# Sheet1.net
KiCad netlist of a schematic drawn in Altium Designer
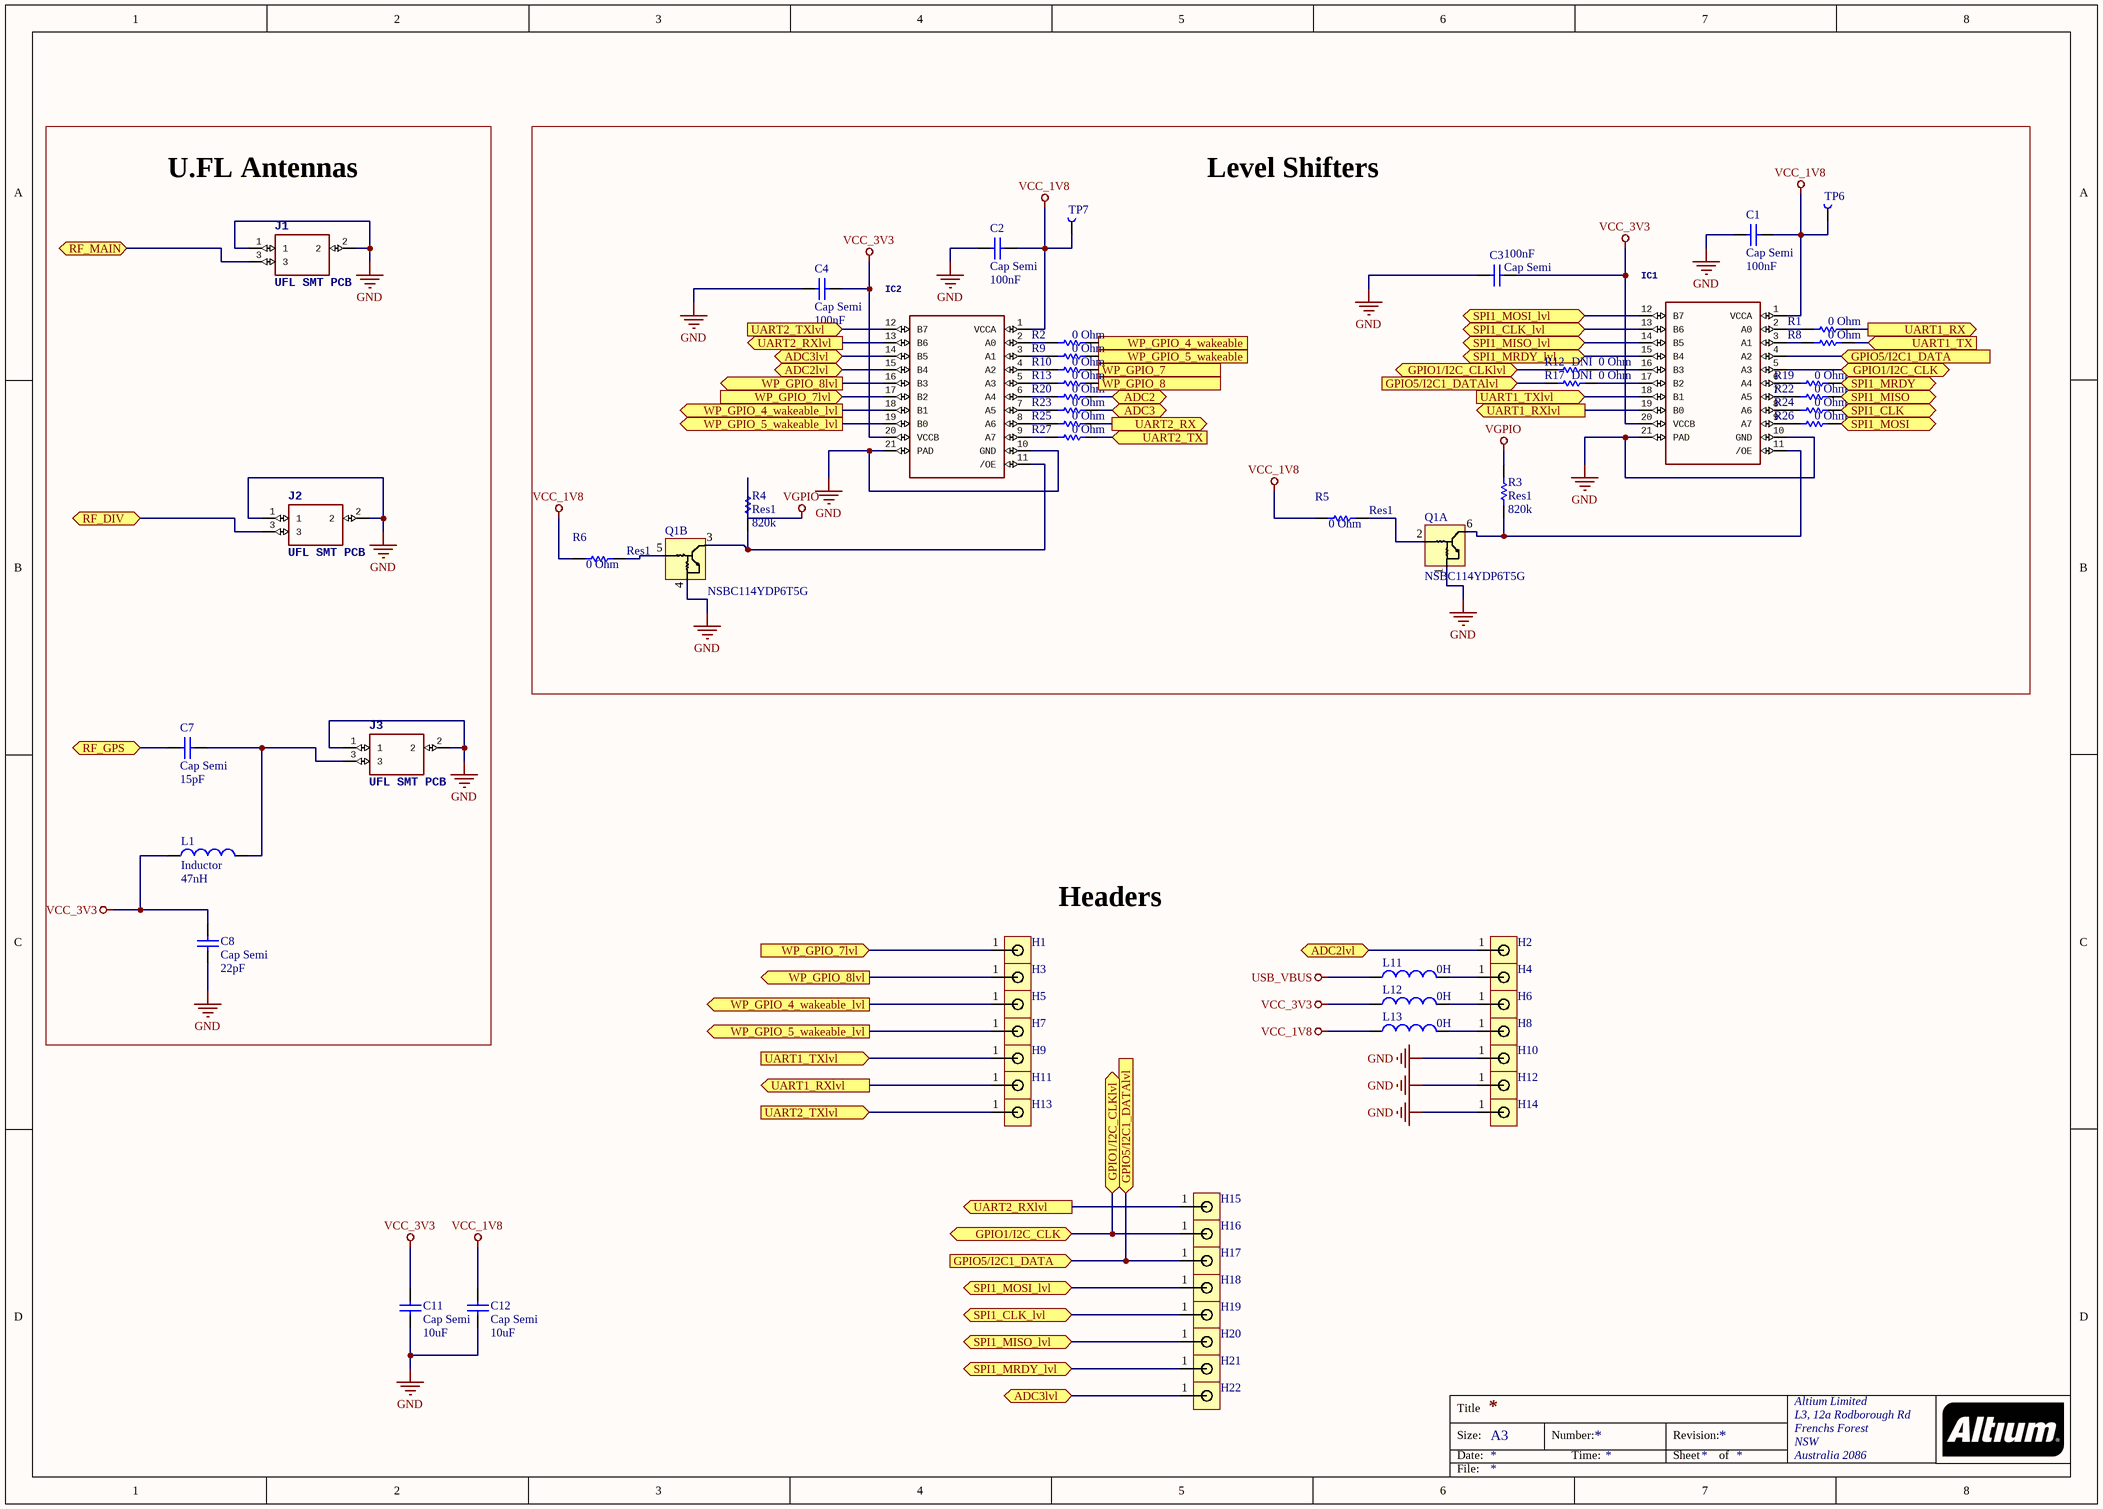
[diagram p0: Sheet1.SchDoc]

(export (version "E")
  (design (tool "Eeschema 10.0.6"))
  (components
    (comp (ref "C1")
      (value "Cap Semi")
      (footprint "CAP 0402/1005")
      (description "0.1µF -20%, +80% 16V Ceramic Capacitor Y5V (F) 0402 (1005 Metric)")
      (fields (field (name "PART NUMBER") "VJ0402V104ZXJCW1BC") (field (name "ALTIUM_VALUE") "100nF"))
      (libsource (lib "Miscellaneous Devices") (part "Cap Semi"))
    )
    (comp (ref "C2")
      (value "Cap Semi")
      (footprint "CAP 0402/1005")
      (description "0.1µF -20%, +80% 16V Ceramic Capacitor Y5V (F) 0402 (1005 Metric)")
      (fields (field (name "PART NUMBER") "VJ0402V104ZXJCW1BC") (field (name "ALTIUM_VALUE") "100nF"))
      (libsource (lib "Miscellaneous Devices") (part "Cap Semi"))
    )
    (comp (ref "C3")
      (value "Cap Semi")
      (footprint "CAP 0402/1005")
      (description "0.1µF -20%, +80% 16V Ceramic Capacitor Y5V (F) 0402 (1005 Metric)")
      (fields (field (name "PART NUMBER") "VJ0402V104ZXJCW1BC") (field (name "ALTIUM_VALUE") "100nF"))
      (libsource (lib "Miscellaneous Devices") (part "Cap Semi"))
    )
    (comp (ref "C4")
      (value "Cap Semi")
      (footprint "CAP 0402/1005")
      (description "0.1µF -20%, +80% 16V Ceramic Capacitor Y5V (F) 0402 (1005 Metric)")
      (fields (field (name "PART NUMBER") "VJ0402V104ZXJCW1BC") (field (name "ALTIUM_VALUE") "100nF"))
      (libsource (lib "Miscellaneous Devices") (part "Cap Semi"))
    )
    (comp (ref "C7")
      (value "Cap Semi")
      (footprint "CAP 0402/1005")
      (description "15pF ±5% 50V Ceramic Capacitor C0G, NP0 0402 (1005 Metric)")
      (fields (field (name "PART NUMBER") "UMK105CG150JV-F") (field (name "ALTIUM_VALUE") "15pF"))
      (libsource (lib "Miscellaneous Devices") (part "Cap Semi"))
    )
    (comp (ref "C8")
      (value "Cap Semi")
      (footprint "CAP 0402/1005")
      (description "CAP CER 22PF 50V NP0 0402")
      (fields (field (name "PART NUMBER") "UMK105CG220JV-F") (field (name "ALTIUM_VALUE") "22pF"))
      (libsource (lib "Miscellaneous Devices") (part "Cap Semi"))
    )
    (comp (ref "C11")
      (value "Cap Semi")
      (footprint "CAP 0603/1608")
      (description "10µF ±20% 6.3V Ceramic Capacitor X5R 0603 (1608 Metric)")
      (fields
        (field (name "PART NUMBER") "JMK107BJ106MA-T")
        (field (name "ALTIUM_VALUE") "10uF")
        (field (name "PUBLISHER") "Altium Limited")
      )
      (libsource (lib "Miscellaneous Devices") (part "Cap Semi"))
    )
    (comp (ref "C12")
      (value "Cap Semi")
      (footprint "CAP 0603/1608")
      (description "10µF ±20% 6.3V Ceramic Capacitor X5R 0603 (1608 Metric)")
      (fields
        (field (name "PART NUMBER") "JMK107BJ106MA-T")
        (field (name "ALTIUM_VALUE") "10uF")
        (field (name "PUBLISHER") "Altium Limited")
      )
      (libsource (lib "Miscellaneous Devices") (part "Cap Semi"))
    )
    (comp (ref "H1") (value "Header 1") (footprint "PIN1-3D") (libsource (lib "Header 1") (part "Header 1")))
    (comp (ref "H2") (value "Header 1") (footprint "PIN1-3D") (libsource (lib "Header 1") (part "Header 1")))
    (comp (ref "H3") (value "Header 1") (footprint "PIN1-3D") (libsource (lib "Header 1") (part "Header 1")))
    (comp (ref "H4") (value "Header 1") (footprint "PIN1-3D") (libsource (lib "Header 1") (part "Header 1")))
    (comp (ref "H5") (value "Header 1") (footprint "PIN1-3D") (libsource (lib "Header 1") (part "Header 1")))
    (comp (ref "H6") (value "Header 1") (footprint "PIN1-3D") (libsource (lib "Header 1") (part "Header 1")))
    (comp (ref "H7") (value "Header 1") (footprint "PIN1-3D") (libsource (lib "Header 1") (part "Header 1")))
    (comp (ref "H8") (value "Header 1") (footprint "PIN1-3D") (libsource (lib "Header 1") (part "Header 1")))
    (comp (ref "H9") (value "Header 1") (footprint "PIN1-3D") (libsource (lib "Header 1") (part "Header 1")))
    (comp (ref "H10") (value "Header 1") (footprint "PIN1-3D") (libsource (lib "Header 1") (part "Header 1")))
    (comp (ref "H11") (value "Header 1") (footprint "PIN1-3D") (libsource (lib "Header 1") (part "Header 1")))
    (comp (ref "H12") (value "Header 1") (footprint "PIN1-3D") (libsource (lib "Header 1") (part "Header 1")))
    (comp (ref "H13") (value "Header 1") (footprint "PIN1-3D") (libsource (lib "Header 1") (part "Header 1")))
    (comp (ref "H14") (value "Header 1") (footprint "PIN1-3D") (libsource (lib "Header 1") (part "Header 1")))
    (comp (ref "H15") (value "Header 1") (footprint "PIN1-3D") (libsource (lib "Header 1") (part "Header 1")))
    (comp (ref "H16") (value "Header 1") (footprint "PIN1-3D") (libsource (lib "Header 1") (part "Header 1")))
    (comp (ref "H17") (value "Header 1") (footprint "PIN1-3D") (libsource (lib "Header 1") (part "Header 1")))
    (comp (ref "H18") (value "Header 1") (footprint "PIN1-3D") (libsource (lib "Header 1") (part "Header 1")))
    (comp (ref "H19") (value "Header 1") (footprint "PIN1-3D") (libsource (lib "Header 1") (part "Header 1")))
    (comp (ref "H20") (value "Header 1") (footprint "PIN1-3D") (libsource (lib "Header 1") (part "Header 1")))
    (comp (ref "H21") (value "Header 1") (footprint "PIN1-3D") (libsource (lib "Header 1") (part "Header 1")))
    (comp (ref "H22") (value "Header 1") (footprint "PIN1-3D") (libsource (lib "Header 1") (part "Header 1")))
    (comp (ref "IC1")
      (value "~")
      (footprint "DQFN-20")
      (description "Voltage Level Translator Bidirectional 1 Circuit 8 Channel 100Mbps 20-DQFN (2.5x4.5)")
      (fields (field (name "PART NUMBER") "FXMA108BQX") (field (name "MOUSER_PART_NUMBER") "512-FXMA108BQX"))
      (libsource (lib "FXMA108BQX") (part "FXMA108BQX"))
    )
    (comp (ref "IC2")
      (value "~")
      (footprint "DQFN-20")
      (description "Voltage Level Translator Bidirectional 1 Circuit 8 Channel 100Mbps 20-DQFN (2.5x4.5)")
      (fields (field (name "PART NUMBER") "FXMA108BQX") (field (name "MOUSER_PART_NUMBER") "512-FXMA108BQX"))
      (libsource (lib "FXMA108BQX") (part "FXMA108BQX"))
    )
    (comp (ref "J1")
      (value "UFL SMT PCB")
      (footprint "U.FL-R-SMT-1(10)")
      (description "U.FL (UMCC), IPEX MHF1 Connector Receptacle, Male Pin 50 Ohm Surface Mount Solder")
      (fields
        (field (name "PART NUMBER") "20279-001E-01")
        (field (name "MANUFACTURER_PART_NUMBER") "U.FL-R-SMT-1(10)")
      )
      (libsource (lib "U.FL-R-SMT-1(10)") (part "U.FL-R-SMT-1(10)"))
    )
    (comp (ref "J2")
      (value "UFL SMT PCB")
      (footprint "U.FL-R-SMT-1(10)")
      (description "U.FL (UMCC), IPEX MHF1 Connector Receptacle, Male Pin 50 Ohm Surface Mount Solder")
      (fields
        (field (name "PART NUMBER") "20279-001E-01")
        (field (name "MANUFACTURER_PART_NUMBER") "U.FL-R-SMT-1(10)")
      )
      (libsource (lib "U.FL-R-SMT-1(10)") (part "U.FL-R-SMT-1(10)"))
    )
    (comp (ref "J3")
      (value "UFL SMT PCB")
      (footprint "U.FL-R-SMT-1(10)")
      (description "U.FL (UMCC), IPEX MHF1 Connector Receptacle, Male Pin 50 Ohm Surface Mount Solder")
      (fields
        (field (name "PART NUMBER") "20279-001E-01")
        (field (name "MANUFACTURER_PART_NUMBER") "U.FL-R-SMT-1(10)")
      )
      (libsource (lib "U.FL-R-SMT-1(10)") (part "U.FL-R-SMT-1(10)"))
    )
    (comp (ref "L1")
      (value "Inductor")
      (footprint "IND 0402/1005 RF WW")
      (description "47nH Unshielded Multilayer Inductor 250mA 1.15 Ohm Max 0402 (1005 Metric)")
      (fields (field (name "PART NUMBER") "LQG15HN47NJ02D") (field (name "ALTIUM_VALUE") "47nH"))
      (libsource (lib "Miscellaneous Devices") (part "Inductor"))
    )
    (comp (ref "L11")
      (value "0H")
      (footprint "INDC1608L")
      (description "220 Ohms @ 100MHz 1 Power Line Ferrite Bead 0603 (1608 Metric) 2.2A 50 mOhm")
      (fields
        (field (name "PART NUMBER") "MPZ1608S221ATA00")
        (field (name "Comment") "Inductor")
        (field (name "PUBLISHER") "Altium Limited")
      )
      (libsource (lib "Miscellaneous Devices") (part "Inductor"))
    )
    (comp (ref "L12")
      (value "0H")
      (footprint "INDC1608L")
      (description "220 Ohms @ 100MHz 1 Power Line Ferrite Bead 0603 (1608 Metric) 2.2A 50 mOhm")
      (fields
        (field (name "PART NUMBER") "MPZ1608S221ATA00")
        (field (name "Comment") "Inductor")
        (field (name "PUBLISHER") "Altium Limited")
      )
      (libsource (lib "Miscellaneous Devices") (part "Inductor"))
    )
    (comp (ref "L13")
      (value "0H")
      (footprint "INDC1608L")
      (description "220 Ohms @ 100MHz 1 Power Line Ferrite Bead 0603 (1608 Metric) 2.2A 50 mOhm")
      (fields
        (field (name "PART NUMBER") "MPZ1608S221ATA00")
        (field (name "Comment") "Inductor")
        (field (name "PUBLISHER") "Altium Limited")
      )
      (libsource (lib "Miscellaneous Devices") (part "Inductor"))
    )
    (comp (ref "Q1")
      (value "NSBC114YDP6T5G")
      (footprint "NSBC114YDP6T5G")
      (libsource (lib "") (part "NSBC114YDP6T5G_1"))
    )
    (comp (ref "R1")
      (value "0 Ohm")
      (footprint "RES 0402/1005")
      (description "0 Ohms Jumper  Chip Resistor 0402 (1005 Metric) Automotive AEC-Q200 Metal Element")
      (fields (field (name "PART NUMBER") "RK73Z1ETTP") (field (name "Comment") "Res1"))
      (libsource (lib "Miscellaneous Devices") (part "Res1"))
    )
    (comp (ref "R2")
      (value "0 Ohm")
      (footprint "RES 0402/1005")
      (description "0 Ohms Jumper  Chip Resistor 0402 (1005 Metric) Automotive AEC-Q200 Metal Element")
      (fields (field (name "PART NUMBER") "RK73Z1ETTP") (field (name "Comment") "Res1"))
      (libsource (lib "Miscellaneous Devices") (part "Res1"))
    )
    (comp (ref "R3")
      (value "Res1")
      (footprint "RES 0402/1005")
      (description "820 kOhms ±1% 0.063W, 1/16W Chip Resistor 0402 (1005 Metric) Moisture Resistant Thick Film")
      (fields (field (name "PART NUMBER") "RC0402FR-07820KL") (field (name "ALTIUM_VALUE") "820k"))
      (libsource (lib "Miscellaneous Devices") (part "Res1"))
    )
    (comp (ref "R4")
      (value "Res1")
      (footprint "RES 0402/1005")
      (description "820 kOhms ±1% 0.063W, 1/16W Chip Resistor 0402 (1005 Metric) Moisture Resistant Thick Film")
      (fields (field (name "PART NUMBER") "RC0402FR-07820KL") (field (name "ALTIUM_VALUE") "820k"))
      (libsource (lib "Miscellaneous Devices") (part "Res1"))
    )
    (comp (ref "R5")
      (value "Res1")
      (footprint "RES 0402/1005")
      (description "0 Ohms Jumper  Chip Resistor 0402 (1005 Metric) Automotive AEC-Q200 Metal Element")
      (fields (field (name "PART NUMBER") "RK73Z1ETTP") (field (name "ALTIUM_VALUE") "0 Ohm"))
      (libsource (lib "Miscellaneous Devices") (part "Res1"))
    )
    (comp (ref "R6")
      (value "Res1")
      (footprint "RES 0402/1005")
      (description "0 Ohms Jumper  Chip Resistor 0402 (1005 Metric) Automotive AEC-Q200 Metal Element")
      (fields (field (name "PART NUMBER") "RK73Z1ETTP") (field (name "ALTIUM_VALUE") "0 Ohm"))
      (libsource (lib "Miscellaneous Devices") (part "Res1"))
    )
    (comp (ref "R8")
      (value "0 Ohm")
      (footprint "RES 0402/1005")
      (description "0 Ohms Jumper  Chip Resistor 0402 (1005 Metric) Automotive AEC-Q200 Metal Element")
      (fields (field (name "PART NUMBER") "RK73Z1ETTP") (field (name "Comment") "Res1"))
      (libsource (lib "Miscellaneous Devices") (part "Res1"))
    )
    (comp (ref "R9")
      (value "0 Ohm")
      (footprint "RES 0402/1005")
      (description "0 Ohms Jumper  Chip Resistor 0402 (1005 Metric) Automotive AEC-Q200 Metal Element")
      (fields (field (name "PART NUMBER") "RK73Z1ETTP") (field (name "Comment") "Res1"))
      (libsource (lib "Miscellaneous Devices") (part "Res1"))
    )
    (comp (ref "R10")
      (value "0 Ohm")
      (footprint "RES 0402/1005")
      (description "0 Ohms Jumper  Chip Resistor 0402 (1005 Metric) Automotive AEC-Q200 Metal Element")
      (fields (field (name "PART NUMBER") "RK73Z1ETTP") (field (name "Comment") "Res1"))
      (libsource (lib "Miscellaneous Devices") (part "Res1"))
    )
    (comp (ref "R12")
      (value "DNI")
      (footprint "RES 0402/1005")
      (description "0 Ohms Jumper  Chip Resistor 0402 (1005 Metric) Automotive AEC-Q200 Metal Element")
      (fields (field (name "PART NUMBER") "RK73Z1ETTP") (field (name "ALTIUM_VALUE") "0 Ohm"))
      (libsource (lib "Miscellaneous Devices") (part "Res1"))
    )
    (comp (ref "R13")
      (value "0 Ohm")
      (footprint "RES 0402/1005")
      (description "0 Ohms Jumper  Chip Resistor 0402 (1005 Metric) Automotive AEC-Q200 Metal Element")
      (fields (field (name "PART NUMBER") "RK73Z1ETTP") (field (name "Comment") "Res1"))
      (libsource (lib "Miscellaneous Devices") (part "Res1"))
    )
    (comp (ref "R17")
      (value "DNI")
      (footprint "RES 0402/1005")
      (description "0 Ohms Jumper  Chip Resistor 0402 (1005 Metric) Automotive AEC-Q200 Metal Element")
      (fields (field (name "PART NUMBER") "RK73Z1ETTP") (field (name "ALTIUM_VALUE") "0 Ohm"))
      (libsource (lib "Miscellaneous Devices") (part "Res1"))
    )
    (comp (ref "R19")
      (value "0 Ohm")
      (footprint "RES 0402/1005")
      (description "0 Ohms Jumper  Chip Resistor 0402 (1005 Metric) Automotive AEC-Q200 Metal Element")
      (fields (field (name "PART NUMBER") "RK73Z1ETTP") (field (name "Comment") "Res1"))
      (libsource (lib "Miscellaneous Devices") (part "Res1"))
    )
    (comp (ref "R20")
      (value "0 Ohm")
      (footprint "RES 0402/1005")
      (description "0 Ohms Jumper  Chip Resistor 0402 (1005 Metric) Automotive AEC-Q200 Metal Element")
      (fields (field (name "PART NUMBER") "RK73Z1ETTP") (field (name "Comment") "Res1"))
      (libsource (lib "Miscellaneous Devices") (part "Res1"))
    )
    (comp (ref "R22")
      (value "0 Ohm")
      (footprint "RES 0402/1005")
      (description "0 Ohms Jumper  Chip Resistor 0402 (1005 Metric) Automotive AEC-Q200 Metal Element")
      (fields (field (name "PART NUMBER") "RK73Z1ETTP") (field (name "Comment") "Res1"))
      (libsource (lib "Miscellaneous Devices") (part "Res1"))
    )
    (comp (ref "R23")
      (value "0 Ohm")
      (footprint "RES 0402/1005")
      (description "0 Ohms Jumper  Chip Resistor 0402 (1005 Metric) Automotive AEC-Q200 Metal Element")
      (fields (field (name "PART NUMBER") "RK73Z1ETTP") (field (name "Comment") "Res1"))
      (libsource (lib "Miscellaneous Devices") (part "Res1"))
    )
    (comp (ref "R24")
      (value "0 Ohm")
      (footprint "RES 0402/1005")
      (description "0 Ohms Jumper  Chip Resistor 0402 (1005 Metric) Automotive AEC-Q200 Metal Element")
      (fields (field (name "PART NUMBER") "RK73Z1ETTP") (field (name "Comment") "Res1"))
      (libsource (lib "Miscellaneous Devices") (part "Res1"))
    )
    (comp (ref "R25")
      (value "0 Ohm")
      (footprint "RES 0402/1005")
      (description "0 Ohms Jumper  Chip Resistor 0402 (1005 Metric) Automotive AEC-Q200 Metal Element")
      (fields (field (name "PART NUMBER") "RK73Z1ETTP") (field (name "Comment") "Res1"))
      (libsource (lib "Miscellaneous Devices") (part "Res1"))
    )
    (comp (ref "R26")
      (value "0 Ohm")
      (footprint "RES 0402/1005")
      (description "0 Ohms Jumper  Chip Resistor 0402 (1005 Metric) Automotive AEC-Q200 Metal Element")
      (fields (field (name "PART NUMBER") "RK73Z1ETTP") (field (name "Comment") "Res1"))
      (libsource (lib "Miscellaneous Devices") (part "Res1"))
    )
    (comp (ref "R27")
      (value "0 Ohm")
      (footprint "RES 0402/1005")
      (description "0 Ohms Jumper  Chip Resistor 0402 (1005 Metric) Automotive AEC-Q200 Metal Element")
      (fields (field (name "PART NUMBER") "RK73Z1ETTP") (field (name "Comment") "Res1"))
      (libsource (lib "Miscellaneous Devices") (part "Res1"))
    )
    (comp (ref "TP6")
      (value "TestPoint")
      (footprint "TestPoint")
      (libsource (lib "TestPoint") (part "TestPoint"))
    )
    (comp (ref "TP7")
      (value "TestPoint")
      (footprint "TestPoint")
      (libsource (lib "TestPoint") (part "TestPoint"))
    )
  )
  (nets
    (net (code "1") (name "/ADC2") (class "Default")
      (node (ref "R20") (pin "2") (pinfunction "2_2") (pintype "passive"))
    )
    (net (code "2") (name "/ADC2lvl") (class "Default")
      (node (ref "H2") (pin "1") (pinfunction "1_1") (pintype "passive"))
      (node (ref "IC2") (pin "15") (pinfunction "B4_15") (pintype "bidirectional"))
    )
    (net (code "3") (name "/ADC3") (class "Default")
      (node (ref "R23") (pin "2") (pinfunction "2_2") (pintype "passive"))
    )
    (net (code "4") (name "/ADC3lvl") (class "Default")
      (node (ref "H22") (pin "1") (pinfunction "1_1") (pintype "passive"))
      (node (ref "IC2") (pin "14") (pinfunction "B5_14") (pintype "bidirectional"))
    )
    (net (code "5") (name "/GPIO1{slash}I2C_CLK") (class "Default")
      (node (ref "H16") (pin "1") (pinfunction "1_1") (pintype "passive"))
      (node (ref "IC1") (pin "5") (pinfunction "A3_5") (pintype "bidirectional"))
      (node (ref "R12") (pin "1") (pinfunction "1_1") (pintype "passive"))
    )
    (net (code "6") (name "/GPIO5{slash}I2C1_DATA") (class "Default")
      (node (ref "H17") (pin "1") (pinfunction "1_1") (pintype "passive"))
      (node (ref "IC1") (pin "4") (pinfunction "A2_4") (pintype "bidirectional"))
      (node (ref "R17") (pin "1") (pinfunction "1_1") (pintype "passive"))
    )
    (net (code "7") (name "/RF_DIV") (class "Default")
      (node (ref "J2") (pin "3") (pinfunction "3_3") (pintype "bidirectional"))
    )
    (net (code "8") (name "/RF_GPS") (class "Default")
      (node (ref "C7") (pin "2") (pinfunction "2_2") (pintype "passive"))
    )
    (net (code "9") (name "/RF_MAIN") (class "Default")
      (node (ref "J1") (pin "3") (pinfunction "3_3") (pintype "bidirectional"))
    )
    (net (code "10") (name "/SPI1_CLK") (class "Default")
      (node (ref "R24") (pin "2") (pinfunction "2_2") (pintype "passive"))
    )
    (net (code "11") (name "/SPI1_CLK_lvl") (class "Default")
      (node (ref "H19") (pin "1") (pinfunction "1_1") (pintype "passive"))
      (node (ref "IC1") (pin "13") (pinfunction "B6_13") (pintype "bidirectional"))
    )
    (net (code "12") (name "/SPI1_MISO") (class "Default")
      (node (ref "R22") (pin "2") (pinfunction "2_2") (pintype "passive"))
    )
    (net (code "13") (name "/SPI1_MISO_lvl") (class "Default")
      (node (ref "H20") (pin "1") (pinfunction "1_1") (pintype "passive"))
      (node (ref "IC1") (pin "14") (pinfunction "B5_14") (pintype "bidirectional"))
    )
    (net (code "14") (name "/SPI1_MOSI") (class "Default")
      (node (ref "R26") (pin "2") (pinfunction "2_2") (pintype "passive"))
    )
    (net (code "15") (name "/SPI1_MOSI_lvl") (class "Default")
      (node (ref "H18") (pin "1") (pinfunction "1_1") (pintype "passive"))
      (node (ref "IC1") (pin "12") (pinfunction "B7_12") (pintype "bidirectional"))
    )
    (net (code "16") (name "/SPI1_MRDY") (class "Default")
      (node (ref "R19") (pin "2") (pinfunction "2_2") (pintype "passive"))
    )
    (net (code "17") (name "/SPI1_MRDY_lvl") (class "Default")
      (node (ref "H21") (pin "1") (pinfunction "1_1") (pintype "passive"))
      (node (ref "IC1") (pin "15") (pinfunction "B4_15") (pintype "bidirectional"))
    )
    (net (code "18") (name "/UART1_RX") (class "Default")
      (node (ref "R1") (pin "2") (pinfunction "2_2") (pintype "passive"))
    )
    (net (code "19") (name "/UART1_RXlvl") (class "Default")
      (node (ref "H11") (pin "1") (pinfunction "1_1") (pintype "passive"))
      (node (ref "IC1") (pin "19") (pinfunction "B0_19") (pintype "bidirectional"))
    )
    (net (code "20") (name "/UART1_TX") (class "Default")
      (node (ref "R8") (pin "2") (pinfunction "2_2") (pintype "passive"))
    )
    (net (code "21") (name "/UART1_TXlvl") (class "Default")
      (node (ref "H9") (pin "1") (pinfunction "1_1") (pintype "passive"))
      (node (ref "IC1") (pin "18") (pinfunction "B1_18") (pintype "bidirectional"))
    )
    (net (code "22") (name "/UART2_RX") (class "Default")
      (node (ref "R25") (pin "2") (pinfunction "2_2") (pintype "passive"))
    )
    (net (code "23") (name "/UART2_RXlvl") (class "Default")
      (node (ref "H15") (pin "1") (pinfunction "1_1") (pintype "passive"))
      (node (ref "IC2") (pin "13") (pinfunction "B6_13") (pintype "bidirectional"))
    )
    (net (code "24") (name "/UART2_TX") (class "Default")
      (node (ref "R27") (pin "2") (pinfunction "2_2") (pintype "passive"))
    )
    (net (code "25") (name "/UART2_TXlvl") (class "Default")
      (node (ref "H13") (pin "1") (pinfunction "1_1") (pintype "passive"))
      (node (ref "IC2") (pin "12") (pinfunction "B7_12") (pintype "bidirectional"))
    )
    (net (code "26") (name "/WP_GPIO_4_wakeable") (class "Default")
      (node (ref "R2") (pin "2") (pinfunction "2_2") (pintype "passive"))
    )
    (net (code "27") (name "/WP_GPIO_4_wakeable_lvl") (class "Default")
      (node (ref "H5") (pin "1") (pinfunction "1_1") (pintype "passive"))
      (node (ref "IC2") (pin "18") (pinfunction "B1_18") (pintype "bidirectional"))
    )
    (net (code "28") (name "/WP_GPIO_5_wakeable") (class "Default")
      (node (ref "R9") (pin "2") (pinfunction "2_2") (pintype "passive"))
    )
    (net (code "29") (name "/WP_GPIO_5_wakeable_lvl") (class "Default")
      (node (ref "H7") (pin "1") (pinfunction "1_1") (pintype "passive"))
      (node (ref "IC2") (pin "19") (pinfunction "B0_19") (pintype "bidirectional"))
    )
    (net (code "30") (name "/WP_GPIO_7") (class "Default")
      (node (ref "R10") (pin "2") (pinfunction "2_2") (pintype "passive"))
    )
    (net (code "31") (name "/WP_GPIO_7lvl") (class "Default")
      (node (ref "H1") (pin "1") (pinfunction "1_1") (pintype "passive"))
      (node (ref "IC2") (pin "17") (pinfunction "B2_17") (pintype "bidirectional"))
    )
    (net (code "32") (name "/WP_GPIO_8") (class "Default")
      (node (ref "R13") (pin "2") (pinfunction "2_2") (pintype "passive"))
    )
    (net (code "33") (name "/WP_GPIO_8lvl") (class "Default")
      (node (ref "H3") (pin "1") (pinfunction "1_1") (pintype "passive"))
      (node (ref "IC2") (pin "16") (pinfunction "B3_16") (pintype "bidirectional"))
    )
    (net (code "34") (name "GND") (class "Default")
      (node (ref "C1") (pin "2") (pinfunction "2_2") (pintype "passive"))
      (node (ref "C11") (pin "1") (pinfunction "1_1") (pintype "passive"))
      (node (ref "C12") (pin "1") (pinfunction "1_1") (pintype "passive"))
      (node (ref "C2") (pin "2") (pinfunction "2_2") (pintype "passive"))
      (node (ref "C3") (pin "2") (pinfunction "2_2") (pintype "passive"))
      (node (ref "C4") (pin "2") (pinfunction "2_2") (pintype "passive"))
      (node (ref "C8") (pin "2") (pinfunction "2_2") (pintype "passive"))
      (node (ref "H10") (pin "1") (pinfunction "1_1") (pintype "passive"))
      (node (ref "H12") (pin "1") (pinfunction "1_1") (pintype "passive"))
      (node (ref "H14") (pin "1") (pinfunction "1_1") (pintype "passive"))
      (node (ref "IC1") (pin "10") (pinfunction "GND_10") (pintype "bidirectional"))
      (node (ref "IC1") (pin "21") (pinfunction "PAD_21") (pintype "bidirectional"))
      (node (ref "IC2") (pin "10") (pinfunction "GND_10") (pintype "bidirectional"))
      (node (ref "IC2") (pin "21") (pinfunction "PAD_21") (pintype "bidirectional"))
      (node (ref "J1") (pin "1") (pinfunction "1_1") (pintype "bidirectional"))
      (node (ref "J1") (pin "2") (pinfunction "2_2") (pintype "bidirectional"))
      (node (ref "J2") (pin "1") (pinfunction "1_1") (pintype "bidirectional"))
      (node (ref "J2") (pin "2") (pinfunction "2_2") (pintype "bidirectional"))
      (node (ref "J3") (pin "1") (pinfunction "1_1") (pintype "bidirectional"))
      (node (ref "J3") (pin "2") (pinfunction "2_2") (pintype "bidirectional"))
      (node (ref "Q1") (pin "1") (pintype "passive"))
      (node (ref "Q1") (pin "4") (pintype "passive"))
    )
    (net (code "35") (name "Net-(C7-Pad1)") (class "Default")
      (node (ref "C7") (pin "1") (pinfunction "1_1") (pintype "passive"))
      (node (ref "J3") (pin "3") (pinfunction "3_3") (pintype "bidirectional"))
      (node (ref "L1") (pin "2") (pinfunction "2_2") (pintype "passive"))
    )
    (net (code "36") (name "Net-(H4-Pad1)") (class "Default")
      (node (ref "H4") (pin "1") (pinfunction "1_1") (pintype "passive"))
      (node (ref "L11") (pin "2") (pinfunction "2_2") (pintype "passive"))
    )
    (net (code "37") (name "Net-(H6-Pad1)") (class "Default")
      (node (ref "H6") (pin "1") (pinfunction "1_1") (pintype "passive"))
      (node (ref "L12") (pin "2") (pinfunction "2_2") (pintype "passive"))
    )
    (net (code "38") (name "Net-(H8-Pad1)") (class "Default")
      (node (ref "H8") (pin "1") (pinfunction "1_1") (pintype "passive"))
      (node (ref "L13") (pin "2") (pinfunction "2_2") (pintype "passive"))
    )
    (net (code "39") (name "Net-(IC1-A0)") (class "Default")
      (node (ref "IC1") (pin "2") (pinfunction "A0_2") (pintype "bidirectional"))
      (node (ref "R1") (pin "1") (pinfunction "1_1") (pintype "passive"))
    )
    (net (code "40") (name "Net-(IC1-A1)") (class "Default")
      (node (ref "IC1") (pin "3") (pinfunction "A1_3") (pintype "bidirectional"))
      (node (ref "R8") (pin "1") (pinfunction "1_1") (pintype "passive"))
    )
    (net (code "41") (name "Net-(IC1-A4)") (class "Default")
      (node (ref "IC1") (pin "6") (pinfunction "A4_6") (pintype "bidirectional"))
      (node (ref "R19") (pin "1") (pinfunction "1_1") (pintype "passive"))
    )
    (net (code "42") (name "Net-(IC1-A5)") (class "Default")
      (node (ref "IC1") (pin "7") (pinfunction "A5_7") (pintype "bidirectional"))
      (node (ref "R22") (pin "1") (pinfunction "1_1") (pintype "passive"))
    )
    (net (code "43") (name "Net-(IC1-A6)") (class "Default")
      (node (ref "IC1") (pin "8") (pinfunction "A6_8") (pintype "bidirectional"))
      (node (ref "R24") (pin "1") (pinfunction "1_1") (pintype "passive"))
    )
    (net (code "44") (name "Net-(IC1-A7)") (class "Default")
      (node (ref "IC1") (pin "9") (pinfunction "A7_9") (pintype "bidirectional"))
      (node (ref "R26") (pin "1") (pinfunction "1_1") (pintype "passive"))
    )
    (net (code "45") (name "Net-(IC1-B2)") (class "Default")
      (node (ref "IC1") (pin "17") (pinfunction "B2_17") (pintype "bidirectional"))
      (node (ref "R17") (pin "2") (pinfunction "2_2") (pintype "passive"))
    )
    (net (code "46") (name "Net-(IC1-B3)") (class "Default")
      (node (ref "IC1") (pin "16") (pinfunction "B3_16") (pintype "bidirectional"))
      (node (ref "R12") (pin "2") (pinfunction "2_2") (pintype "passive"))
    )
    (net (code "47") (name "Net-(IC1-{slash}OE)") (class "Default")
      (node (ref "IC1") (pin "11") (pinfunction "/OE_11") (pintype "bidirectional"))
      (node (ref "Q1") (pin "6") (pintype "passive"))
      (node (ref "R3") (pin "1") (pinfunction "1_1") (pintype "passive"))
    )
    (net (code "48") (name "Net-(IC2-A0)") (class "Default")
      (node (ref "IC2") (pin "2") (pinfunction "A0_2") (pintype "bidirectional"))
      (node (ref "R2") (pin "1") (pinfunction "1_1") (pintype "passive"))
    )
    (net (code "49") (name "Net-(IC2-A1)") (class "Default")
      (node (ref "IC2") (pin "3") (pinfunction "A1_3") (pintype "bidirectional"))
      (node (ref "R9") (pin "1") (pinfunction "1_1") (pintype "passive"))
    )
    (net (code "50") (name "Net-(IC2-A2)") (class "Default")
      (node (ref "IC2") (pin "4") (pinfunction "A2_4") (pintype "bidirectional"))
      (node (ref "R10") (pin "1") (pinfunction "1_1") (pintype "passive"))
    )
    (net (code "51") (name "Net-(IC2-A3)") (class "Default")
      (node (ref "IC2") (pin "5") (pinfunction "A3_5") (pintype "bidirectional"))
      (node (ref "R13") (pin "1") (pinfunction "1_1") (pintype "passive"))
    )
    (net (code "52") (name "Net-(IC2-A4)") (class "Default")
      (node (ref "IC2") (pin "6") (pinfunction "A4_6") (pintype "bidirectional"))
      (node (ref "R20") (pin "1") (pinfunction "1_1") (pintype "passive"))
    )
    (net (code "53") (name "Net-(IC2-A5)") (class "Default")
      (node (ref "IC2") (pin "7") (pinfunction "A5_7") (pintype "bidirectional"))
      (node (ref "R23") (pin "1") (pinfunction "1_1") (pintype "passive"))
    )
    (net (code "54") (name "Net-(IC2-A6)") (class "Default")
      (node (ref "IC2") (pin "8") (pinfunction "A6_8") (pintype "bidirectional"))
      (node (ref "R25") (pin "1") (pinfunction "1_1") (pintype "passive"))
    )
    (net (code "55") (name "Net-(IC2-A7)") (class "Default")
      (node (ref "IC2") (pin "9") (pinfunction "A7_9") (pintype "bidirectional"))
      (node (ref "R27") (pin "1") (pinfunction "1_1") (pintype "passive"))
    )
    (net (code "56") (name "Net-(IC2-{slash}OE)") (class "Default")
      (node (ref "IC2") (pin "11") (pinfunction "/OE_11") (pintype "bidirectional"))
      (node (ref "Q1") (pin "3") (pintype "passive"))
      (node (ref "R4") (pin "1") (pinfunction "1_1") (pintype "passive"))
    )
    (net (code "57") (name "Net-(Q1-Pad2)") (class "Default")
      (node (ref "Q1") (pin "2") (pintype "passive"))
      (node (ref "R5") (pin "2") (pinfunction "2_2") (pintype "passive"))
    )
    (net (code "58") (name "Net-(Q1-Pad5)") (class "Default")
      (node (ref "Q1") (pin "5") (pintype "passive"))
      (node (ref "R6") (pin "2") (pinfunction "2_2") (pintype "passive"))
    )
    (net (code "59") (name "USB_VBUS") (class "Default")
      (node (ref "L11") (pin "1") (pinfunction "1_1") (pintype "passive"))
    )
    (net (code "60") (name "VCC_1V8") (class "Default")
      (node (ref "C1") (pin "1") (pinfunction "1_1") (pintype "passive"))
      (node (ref "C12") (pin "2") (pinfunction "2_2") (pintype "passive"))
      (node (ref "C2") (pin "1") (pinfunction "1_1") (pintype "passive"))
      (node (ref "IC1") (pin "1") (pinfunction "VCCA_1") (pintype "bidirectional"))
      (node (ref "IC2") (pin "1") (pinfunction "VCCA_1") (pintype "bidirectional"))
      (node (ref "L13") (pin "1") (pinfunction "1_1") (pintype "passive"))
      (node (ref "R5") (pin "1") (pinfunction "1_1") (pintype "passive"))
      (node (ref "R6") (pin "1") (pinfunction "1_1") (pintype "passive"))
      (node (ref "TP6") (pin "1") (pinfunction "TP_1") (pintype "passive"))
      (node (ref "TP7") (pin "1") (pinfunction "TP_1") (pintype "passive"))
    )
    (net (code "61") (name "VCC_3V3") (class "Default")
      (node (ref "C11") (pin "2") (pinfunction "2_2") (pintype "passive"))
      (node (ref "C3") (pin "1") (pinfunction "1_1") (pintype "passive"))
      (node (ref "C4") (pin "1") (pinfunction "1_1") (pintype "passive"))
      (node (ref "C8") (pin "1") (pinfunction "1_1") (pintype "passive"))
      (node (ref "IC1") (pin "20") (pinfunction "VCCB_20") (pintype "bidirectional"))
      (node (ref "IC2") (pin "20") (pinfunction "VCCB_20") (pintype "bidirectional"))
      (node (ref "L1") (pin "1") (pinfunction "1_1") (pintype "passive"))
      (node (ref "L12") (pin "1") (pinfunction "1_1") (pintype "passive"))
    )
    (net (code "62") (name "VGPIO") (class "Default")
      (node (ref "R3") (pin "2") (pinfunction "2_2") (pintype "passive"))
      (node (ref "R4") (pin "2") (pinfunction "2_2") (pintype "passive"))
    )
  )
)
